# Analog-RGB-Mixer.net
KiCad netlist of a schematic drawn in EAGLE
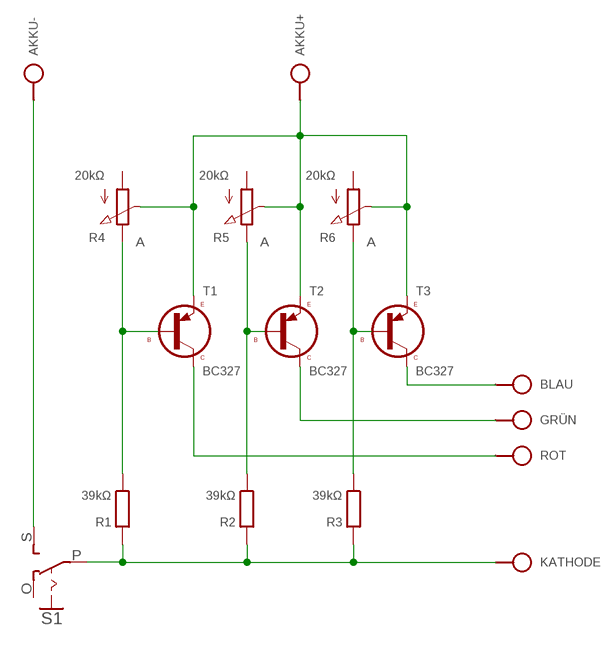
[diagram p0: schematic, sheet 1]

(export (version "E")
  (design (tool "Eeschema 10.0.6"))
  (components
    (comp (ref "AKKU")
      (value "SPAD+--+")
      (footprint "eagle-import:SPAD-+")
      (libsource (lib "eagle-import") (part "SPAD+--+"))
    )
    (comp (ref "BLAU")
      (value "HPORT")
      (footprint "eagle-import:SPAD")
      (libsource (lib "eagle-import") (part "HPORT"))
    )
    (comp (ref "GRÜN")
      (value "HPORT")
      (footprint "eagle-import:SPAD")
      (libsource (lib "eagle-import") (part "HPORT"))
    )
    (comp (ref "KATHODE")
      (value "HPORT")
      (footprint "eagle-import:SPAD")
      (libsource (lib "eagle-import") (part "HPORT"))
    )
    (comp (ref "R1")
      (value "39kΩ")
      (footprint "eagle-import:0204_5")
      (libsource (lib "eagle-import") (part "R0204/5"))
    )
    (comp (ref "R2")
      (value "39kΩ")
      (footprint "eagle-import:0204_12-V")
      (libsource (lib "eagle-import") (part "R0204/12-V"))
    )
    (comp (ref "R3")
      (value "39kΩ")
      (footprint "eagle-import:0204_20-V")
      (libsource (lib "eagle-import") (part "R0204/20-V"))
    )
    (comp (ref "R4")
      (value "20kΩ")
      (footprint "eagle-import:CONN-2P")
      (libsource (lib "eagle-import") (part "POT2A-2P"))
    )
    (comp (ref "R5")
      (value "20kΩ")
      (footprint "eagle-import:CONN-2P")
      (libsource (lib "eagle-import") (part "POT2A-2P"))
    )
    (comp (ref "R6")
      (value "20kΩ")
      (footprint "eagle-import:CONN-2P")
      (libsource (lib "eagle-import") (part "POT2A-2P"))
    )
    (comp (ref "ROT")
      (value "HPORT")
      (footprint "eagle-import:SPAD")
      (libsource (lib "eagle-import") (part "HPORT"))
    )
    (comp (ref "S1")
      (value "SL-SW-1P-2T-H")
      (footprint "eagle-import:SLSW-1P2T-H")
      (libsource (lib "eagle-import") (part "SL-SW-1P-2T-H"))
    )
    (comp (ref "T1")
      (value "BC327")
      (footprint "eagle-import:TO92")
      (libsource (lib "eagle-import") (part "BC327"))
    )
    (comp (ref "T2")
      (value "BC327")
      (footprint "eagle-import:TO92")
      (libsource (lib "eagle-import") (part "BC327"))
    )
    (comp (ref "T3")
      (value "BC327")
      (footprint "eagle-import:TO92")
      (libsource (lib "eagle-import") (part "BC327"))
    )
  )
  (nets
    (net (code "1") (name "Net-(AKKUA-P$1)") (class "Default")
      (node (ref "AKKU") (pin "2") (pinfunction "P$1_2") (pintype "passive"))
      (node (ref "R4") (pin "2") (pinfunction "S_2") (pintype "passive"))
      (node (ref "R5") (pin "2") (pinfunction "S_2") (pintype "passive"))
      (node (ref "R6") (pin "2") (pinfunction "S_2") (pintype "passive"))
      (node (ref "T1") (pin "3") (pinfunction "E_3") (pintype "passive"))
      (node (ref "T2") (pin "3") (pinfunction "E_3") (pintype "passive"))
      (node (ref "T3") (pin "3") (pinfunction "E_3") (pintype "passive"))
    )
    (net (code "2") (name "Net-(AKKUB-P$1)") (class "Default")
      (node (ref "AKKU") (pin "1") (pinfunction "P$1_1") (pintype "passive"))
      (node (ref "S1") (pin "S") (pinfunction "S_S") (pintype "passive"))
    )
    (net (code "3") (name "Net-(BLAU-P$1)") (class "Default")
      (node (ref "BLAU") (pin "1") (pinfunction "P$1_1") (pintype "passive"))
      (node (ref "T3") (pin "1") (pinfunction "C_1") (pintype "passive"))
    )
    (net (code "4") (name "Net-(GRÜN-P$1)") (class "Default")
      (node (ref "GRÜN") (pin "1") (pinfunction "P$1_1") (pintype "passive"))
      (node (ref "T2") (pin "1") (pinfunction "C_1") (pintype "passive"))
    )
    (net (code "5") (name "Net-(KATHODE-P$1)") (class "Default")
      (node (ref "KATHODE") (pin "1") (pinfunction "P$1_1") (pintype "passive"))
      (node (ref "R1") (pin "1") (pinfunction "2_1") (pintype "passive"))
      (node (ref "R2") (pin "1") (pinfunction "2_1") (pintype "passive"))
      (node (ref "R3") (pin "2") (pinfunction "2_2") (pintype "passive"))
      (node (ref "S1") (pin "P") (pinfunction "P_P") (pintype "passive"))
    )
    (net (code "6") (name "Net-(R1-1)") (class "Default")
      (node (ref "R1") (pin "2") (pinfunction "1_2") (pintype "passive"))
      (node (ref "R4") (pin "1") (pinfunction "A_1") (pintype "passive"))
      (node (ref "T1") (pin "2") (pinfunction "B_2") (pintype "passive"))
    )
    (net (code "7") (name "Net-(R2-1)") (class "Default")
      (node (ref "R2") (pin "2") (pinfunction "1_2") (pintype "passive"))
      (node (ref "R5") (pin "1") (pinfunction "A_1") (pintype "passive"))
      (node (ref "T2") (pin "2") (pinfunction "B_2") (pintype "passive"))
    )
    (net (code "8") (name "Net-(R6-A)") (class "Default")
      (node (ref "R3") (pin "1") (pinfunction "1_1") (pintype "passive"))
      (node (ref "R6") (pin "1") (pinfunction "A_1") (pintype "passive"))
      (node (ref "T3") (pin "2") (pinfunction "B_2") (pintype "passive"))
    )
    (net (code "9") (name "Net-(ROT-P$1)") (class "Default")
      (node (ref "ROT") (pin "1") (pinfunction "P$1_1") (pintype "passive"))
      (node (ref "T1") (pin "1") (pinfunction "C_1") (pintype "passive"))
    )
    (net (code "10") (name "unconnected-(S1-PadO)") (class "Default")
      (node (ref "S1") (pin "O") (pinfunction "O_O") (pintype "passive"))
    )
  )
)
